# PWR_M_V1.net
KiCad netlist of a schematic drawn in Altium Designer
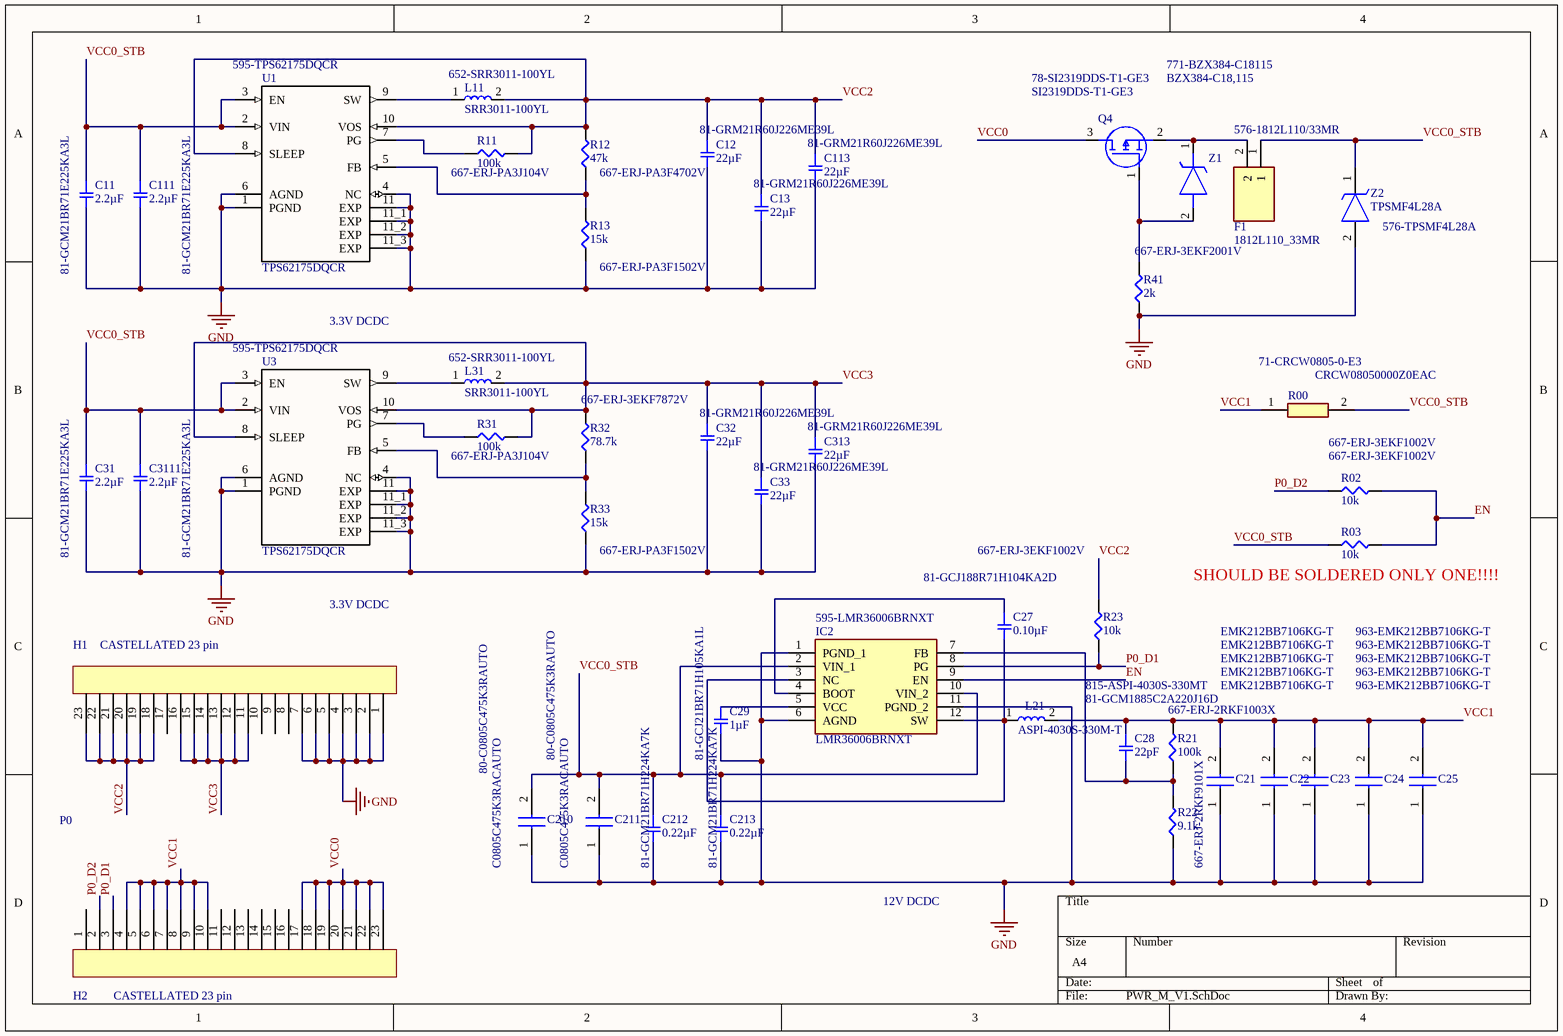
[diagram p0: PWR_M_V1.SchDoc]

(export (version "E")
  (design (tool "Eeschema 10.0.6"))
  (components
    (comp (ref "C11")
      (value "2.2µF")
      (footprint "SMD-0805C")
      (description "CAP CER 2.2UF 25V X7R 0805")
      (fields
        (field (name "DIGI-KEY PART NUMBER") "490-4787-1-ND")
        (field (name "PART NUMBER") "GCM21BR71E225KA73L")
        (field (name "SUPPLIER PART NUMBER 1") "81-GCM21BR71E225KA3L")
      )
      (libsource (lib "capacitor_murata_0805") (part "GCM21BR71E225KA73L"))
    )
    (comp (ref "C12")
      (value "22µF")
      (footprint "SMD-0805C")
      (description "CAP CER 22UF 6.3V X5R 0805")
      (fields
        (field (name "PART NUMBER") "GRM21BR60J226ME39L")
        (field (name "DIGI-KEY PART NUMBER") "490-1719-1-ND")
        (field (name "SUPPLIER PART NUMBER 1") "81-GRM21R60J226ME39L")
      )
      (libsource (lib "cap_murata") (part "CAPACITOR"))
    )
    (comp (ref "C13")
      (value "22µF")
      (footprint "SMD-0805C")
      (description "CAP CER 22UF 6.3V X5R 0805")
      (fields
        (field (name "PART NUMBER") "GRM21BR60J226ME39L")
        (field (name "DIGI-KEY PART NUMBER") "490-1719-1-ND")
        (field (name "SUPPLIER PART NUMBER 1") "81-GRM21R60J226ME39L")
      )
      (libsource (lib "cap_murata") (part "CAPACITOR"))
    )
    (comp (ref "C21")
      (value "EMK212BB7106KG-T")
      (footprint "SamacSys:CAPC2012X135N")
      (description "Capacitor")
      (fields (field (name "SUPPLIER PART NUMBER 1") "963-EMK212BB7106KG-T"))
      (libsource (lib "*") (part "EMK212BB7106KG-T"))
    )
    (comp (ref "C22")
      (value "EMK212BB7106KG-T")
      (footprint "SamacSys:CAPC2012X135N")
      (description "Capacitor")
      (fields (field (name "SUPPLIER PART NUMBER 1") "963-EMK212BB7106KG-T"))
      (libsource (lib "*") (part "EMK212BB7106KG-T"))
    )
    (comp (ref "C23")
      (value "EMK212BB7106KG-T")
      (footprint "SamacSys:CAPC2012X135N")
      (description "Capacitor")
      (fields (field (name "SUPPLIER PART NUMBER 1") "963-EMK212BB7106KG-T"))
      (libsource (lib "*") (part "EMK212BB7106KG-T"))
    )
    (comp (ref "C24")
      (value "EMK212BB7106KG-T")
      (footprint "SamacSys:CAPC2012X135N")
      (description "Capacitor")
      (fields (field (name "SUPPLIER PART NUMBER 1") "963-EMK212BB7106KG-T"))
      (libsource (lib "*") (part "EMK212BB7106KG-T"))
    )
    (comp (ref "C25")
      (value "EMK212BB7106KG-T")
      (footprint "SamacSys:CAPC2012X135N")
      (description "Capacitor")
      (fields (field (name "SUPPLIER PART NUMBER 1") "963-EMK212BB7106KG-T"))
      (libsource (lib "*") (part "EMK212BB7106KG-T"))
    )
    (comp (ref "C27")
      (value "0.10µF")
      (footprint "SMD-0603C")
      (description "CAP CER 0.1UF 50V X7R 0603")
      (fields
        (field (name "DIGI-KEY PART NUMBER") "490-5798-1-ND")
        (field (name "PART NUMBER") "GCJ188R71H104KA12D")
        (field (name "SUPPLIER PART NUMBER 1") "81-GCJ188R71H104KA2D")
      )
      (libsource (lib "capacitor_murata_0603") (part "GCJ188R71H104KA12D"))
    )
    (comp (ref "C28")
      (value "22pF")
      (footprint "SMD-0603C")
      (description "CAP CER 22PF 100V NP0 0603")
      (fields
        (field (name "DIGI-KEY PART NUMBER") "490-4942-1-ND")
        (field (name "PART NUMBER") "GCM1885C2A220JA16D")
        (field (name "SUPPLIER PART NUMBER 1") "81-GCM1885C2A220J16D")
      )
      (libsource (lib "capacitor_murata_0603") (part "GCM1885C2A220JA16D"))
    )
    (comp (ref "C29")
      (value "1µF")
      (footprint "SMD-0805C")
      (description "CAP CER 1UF 50V X7R 0805")
      (fields
        (field (name "DIGI-KEY PART NUMBER") "490-10667-1-ND")
        (field (name "PART NUMBER") "GCJ21BR71H105KA01L")
        (field (name "SUPPLIER PART NUMBER 1") "81-GCJ21BR71H105KA1L")
      )
      (libsource (lib "capacitor_murata_0805") (part "GCJ21BR71H105KA01L"))
    )
    (comp (ref "C31")
      (value "2.2µF")
      (footprint "SMD-0805C")
      (description "CAP CER 2.2UF 25V X7R 0805")
      (fields
        (field (name "DIGI-KEY PART NUMBER") "490-4787-1-ND")
        (field (name "PART NUMBER") "GCM21BR71E225KA73L")
        (field (name "SUPPLIER PART NUMBER 1") "81-GCM21BR71E225KA3L")
      )
      (libsource (lib "capacitor_murata_0805") (part "GCM21BR71E225KA73L"))
    )
    (comp (ref "C32")
      (value "22µF")
      (footprint "SMD-0805C")
      (description "CAP CER 22UF 6.3V X5R 0805")
      (fields
        (field (name "PART NUMBER") "GRM21BR60J226ME39L")
        (field (name "DIGI-KEY PART NUMBER") "490-1719-1-ND")
        (field (name "SUPPLIER PART NUMBER 1") "81-GRM21R60J226ME39L")
      )
      (libsource (lib "cap_murata") (part "CAPACITOR"))
    )
    (comp (ref "C33")
      (value "22µF")
      (footprint "SMD-0805C")
      (description "CAP CER 22UF 6.3V X5R 0805")
      (fields
        (field (name "PART NUMBER") "GRM21BR60J226ME39L")
        (field (name "DIGI-KEY PART NUMBER") "490-1719-1-ND")
        (field (name "SUPPLIER PART NUMBER 1") "81-GRM21R60J226ME39L")
      )
      (libsource (lib "cap_murata") (part "CAPACITOR"))
    )
    (comp (ref "C111")
      (value "2.2µF")
      (footprint "SMD-0805C")
      (description "CAP CER 2.2UF 25V X7R 0805")
      (fields
        (field (name "DIGI-KEY PART NUMBER") "490-4787-1-ND")
        (field (name "PART NUMBER") "GCM21BR71E225KA73L")
        (field (name "SUPPLIER PART NUMBER 1") "81-GCM21BR71E225KA3L")
      )
      (libsource (lib "capacitor_murata_0805") (part "GCM21BR71E225KA73L"))
    )
    (comp (ref "C113")
      (value "22µF")
      (footprint "SMD-0805C")
      (description "CAP CER 22UF 6.3V X5R 0805")
      (fields
        (field (name "PART NUMBER") "GRM21BR60J226ME39L")
        (field (name "DIGI-KEY PART NUMBER") "490-1719-1-ND")
        (field (name "SUPPLIER PART NUMBER 1") "81-GRM21R60J226ME39L")
      )
      (libsource (lib "cap_murata") (part "CAPACITOR"))
    )
    (comp (ref "C210")
      (value "C0805C475K3RACAUTO")
      (footprint "SamacSys:CAPC2012X125N")
      (description "Capacitor")
      (fields
        (field (name "MOUSER2 PART NUMBER") "80-C0805C475K3RAUTO")
        (field (name "SUPPLIER PART NUMBER 1") "80-C0805C475K3RAUTO")
      )
      (libsource (lib "*") (part "C0805C475K3RACAUTO"))
    )
    (comp (ref "C211")
      (value "C0805C475K3RACAUTO")
      (footprint "SamacSys:CAPC2012X125N")
      (description "Capacitor")
      (fields
        (field (name "MOUSER2 PART NUMBER") "80-C0805C475K3RAUTO")
        (field (name "SUPPLIER PART NUMBER 1") "80-C0805C475K3RAUTO")
      )
      (libsource (lib "*") (part "C0805C475K3RACAUTO"))
    )
    (comp (ref "C212")
      (value "0.22µF")
      (footprint "SMD-0805C")
      (description "CAP CER 0.22UF 50V X7R 0805")
      (fields
        (field (name "DIGI-KEY PART NUMBER") "490-13311-1-ND")
        (field (name "PART NUMBER") "GCM21BR71H224KA37K")
        (field (name "SUPPLIER PART NUMBER 1") "81-GCM21BR71H224KA7K")
      )
      (libsource (lib "capacitor_murata_0805") (part "GCM21BR71H224KA37K"))
    )
    (comp (ref "C213")
      (value "0.22µF")
      (footprint "SMD-0805C")
      (description "CAP CER 0.22UF 50V X7R 0805")
      (fields
        (field (name "DIGI-KEY PART NUMBER") "490-13311-1-ND")
        (field (name "PART NUMBER") "GCM21BR71H224KA37K")
        (field (name "SUPPLIER PART NUMBER 1") "81-GCM21BR71H224KA7K")
      )
      (libsource (lib "capacitor_murata_0805") (part "GCM21BR71H224KA37K"))
    )
    (comp (ref "C313")
      (value "22µF")
      (footprint "SMD-0805C")
      (description "CAP CER 22UF 6.3V X5R 0805")
      (fields
        (field (name "PART NUMBER") "GRM21BR60J226ME39L")
        (field (name "DIGI-KEY PART NUMBER") "490-1719-1-ND")
        (field (name "SUPPLIER PART NUMBER 1") "81-GRM21R60J226ME39L")
      )
      (libsource (lib "cap_murata") (part "CAPACITOR"))
    )
    (comp (ref "C3111")
      (value "2.2µF")
      (footprint "SMD-0805C")
      (description "CAP CER 2.2UF 25V X7R 0805")
      (fields
        (field (name "DIGI-KEY PART NUMBER") "490-4787-1-ND")
        (field (name "PART NUMBER") "GCM21BR71E225KA73L")
        (field (name "SUPPLIER PART NUMBER 1") "81-GCM21BR71E225KA3L")
      )
      (libsource (lib "capacitor_murata_0805") (part "GCM21BR71E225KA73L"))
    )
    (comp (ref "F1")
      (value "1812L110_33MR")
      (footprint "SamacSys:FUSC4632X200N")
      (description "Fuse")
      (fields
        (field (name "MOUSER2 PART NUMBER") "576-1812L110/33MR")
        (field (name "MANUFACTURER_PART_NUMBER") "1812L110/33MR")
        (field (name "SUPPLIER PART NUMBER 1") "576-1812L110/33MR")
      )
      (libsource (lib "*") (part "1812L110_33MR"))
    )
    (comp (ref "H1")
      (value "CASTELLATED 23 pin")
      (footprint "CASTELLATED 23 pin")
      (libsource (lib "") (part "CASTELLATED 23 pin_1"))
    )
    (comp (ref "H2")
      (value "CASTELLATED 23 pin")
      (footprint "CASTELLATED 23 pin")
      (libsource (lib "USIB") (part "CASTELLATED 23 pin"))
    )
    (comp (ref "IC2")
      (value "LMR36006BRNXT")
      (footprint "SamacSys:LMR36015FSCQRNXTQ1")
      (description "Integrated Circuit")
      (fields
        (field (name "MOUSER2 PART NUMBER") "595-LMR36006BRNXT")
        (field (name "SUPPLIER PART NUMBER 1") "595-LMR36006BRNXT")
      )
      (libsource (lib "*") (part "LMR36006BRNXT"))
    )
    (comp (ref "L11")
      (value "SRR3011-100YL")
      (footprint "SRR3011-100YL")
      (fields (field (name "SUPPLIER PART NUMBER 1") "652-SRR3011-100YL"))
      (libsource (lib "SRR3011-100YL") (part "SRR3011-100YL"))
    )
    (comp (ref "L21")
      (value "ASPI-4030S-330M-T")
      (footprint "INDPM4040X300N")
      (fields (field (name "SUPPLIER PART NUMBER 1") "815-ASPI-4030S-330MT"))
      (libsource (lib "SamacSys") (part "ASPI-4030S-330M-T"))
    )
    (comp (ref "L31")
      (value "SRR3011-100YL")
      (footprint "SRR3011-100YL")
      (fields (field (name "SUPPLIER PART NUMBER 1") "652-SRR3011-100YL"))
      (libsource (lib "SRR3011-100YL") (part "SRR3011-100YL"))
    )
    (comp (ref "Q4")
      (value "SI2319DDS-T1-GE3")
      (footprint "SamacSys:SOT96P240X120-3N")
      (description "MOSFET (P-Channel)")
      (fields (field (name "SUPPLIER PART NUMBER 1") "78-SI2319DDS-T1-GE3"))
      (libsource (lib "*") (part "SI2319DDS-T1-GE3"))
    )
    (comp (ref "R00")
      (value "CRCW08050000Z0EAC")
      (footprint "SamacSys:RESC2012X60N")
      (description "Resistor")
      (fields
        (field (name "MOUSER2 PART NUMBER") "71-CRCW08050000Z0EAC")
        (field (name "SUPPLIER PART NUMBER 1") "71-CRCW0805-0-E3")
      )
      (libsource (lib "*") (part "CRCW08050000Z0EAC"))
    )
    (comp (ref "R02")
      (value "10k")
      (footprint "SMD-0603-RES")
      (description "RES SMD 10K OHM 1% 1/10W 0603")
      (fields
        (field (name "PART NUMBER") "ERJ-3EKF1002V")
        (field (name "DIGI-KEY PART NUMBER") "P10.0KHCT-ND")
        (field (name "SUPPLIER PART NUMBER 1") "667-ERJ-3EKF1002V")
      )
      (libsource (lib "Panasonic_ERJ_0603") (part "ERJ-3EKF1002V"))
    )
    (comp (ref "R03")
      (value "10k")
      (footprint "SMD-0603-RES")
      (description "RES SMD 10K OHM 1% 1/10W 0603")
      (fields
        (field (name "PART NUMBER") "ERJ-3EKF1002V")
        (field (name "DIGI-KEY PART NUMBER") "P10.0KHCT-ND")
        (field (name "SUPPLIER PART NUMBER 1") "667-ERJ-3EKF1002V")
      )
      (libsource (lib "Panasonic_ERJ_0603") (part "ERJ-3EKF1002V"))
    )
    (comp (ref "R11")
      (value "100k")
      (footprint "SMD-0603-RES")
      (description "RES SMD 100K OHM 5% 1/4W 0603")
      (fields
        (field (name "PART NUMBER") "ERJ-PA3J104V")
        (field (name "DIGI-KEY PART NUMBER") "P100KBZCT-ND")
        (field (name "SUPPLIER PART NUMBER 1") "667-ERJ-PA3J104V")
      )
      (libsource (lib "Panasonic_ERJ_0603") (part "ERJ-PA3J104V"))
    )
    (comp (ref "R12")
      (value "47k")
      (footprint "SMD-0603-RES")
      (description "RES SMD 47K OHM 1% 1/4W 0603")
      (fields
        (field (name "PART NUMBER") "ERJ-PA3F4702V")
        (field (name "DIGI-KEY PART NUMBER") "P47KBYCT-ND")
        (field (name "SUPPLIER PART NUMBER 1") "667-ERJ-PA3F4702V")
      )
      (libsource (lib "Panasonic_ERJ_0603") (part "ERJ-PA3F4702V"))
    )
    (comp (ref "R13")
      (value "15k")
      (footprint "SMD-0603-RES")
      (description "RES SMD 15K OHM 1% 1/4W 0603")
      (fields
        (field (name "PART NUMBER") "ERJ-PA3F1502V")
        (field (name "DIGI-KEY PART NUMBER") "P15KBYCT-ND")
        (field (name "SUPPLIER PART NUMBER 1") "667-ERJ-PA3F1502V")
      )
      (libsource (lib "Panasonic_ERJ_0603") (part "ERJ-PA3F1502V"))
    )
    (comp (ref "R21")
      (value "100k")
      (footprint "SMD-0402-RES")
      (description "RES SMD 100K OHM 1% 1/10W 0402")
      (fields
        (field (name "PART NUMBER") "ERJ-2RKF1003X")
        (field (name "DIGI-KEY PART NUMBER") "P100KLCT-ND")
        (field (name "SUPPLIER PART NUMBER 1") "667-ERJ-2RKF1003X")
      )
      (libsource (lib "Panasonic_ERJ_0402") (part "ERJ-2RKF1003X"))
    )
    (comp (ref "R22")
      (value "9.1k")
      (footprint "SMD-0402-RES")
      (description "RES SMD 9.1K OHM 1% 1/10W 0402")
      (fields
        (field (name "PART NUMBER") "ERJ-2RKF9101X")
        (field (name "DIGI-KEY PART NUMBER") "P9.10KLCT-ND")
        (field (name "SUPPLIER PART NUMBER 1") "667-ERJ-2RKF9101X")
      )
      (libsource (lib "Panasonic_ERJ_0402") (part "ERJ-2RKF9101X"))
    )
    (comp (ref "R23")
      (value "10k")
      (footprint "SMD-0603-RES")
      (description "RES SMD 10K OHM 1% 1/10W 0603")
      (fields
        (field (name "PART NUMBER") "ERJ-3EKF1002V")
        (field (name "DIGI-KEY PART NUMBER") "P10.0KHCT-ND")
        (field (name "SUPPLIER PART NUMBER 1") "667-ERJ-3EKF1002V")
      )
      (libsource (lib "Panasonic_ERJ_0603") (part "ERJ-3EKF1002V"))
    )
    (comp (ref "R31")
      (value "100k")
      (footprint "SMD-0603-RES")
      (description "RES SMD 100K OHM 5% 1/4W 0603")
      (fields
        (field (name "PART NUMBER") "ERJ-PA3J104V")
        (field (name "DIGI-KEY PART NUMBER") "P100KBZCT-ND")
        (field (name "SUPPLIER PART NUMBER 1") "667-ERJ-PA3J104V")
      )
      (libsource (lib "Panasonic_ERJ_0603") (part "ERJ-PA3J104V"))
    )
    (comp (ref "R32")
      (value "78.7k")
      (footprint "SMD-0603-RES")
      (description "RES SMD 78.7K OHM 1% 1/10W 0603")
      (fields
        (field (name "PART NUMBER") "ERJ-3EKF7872V")
        (field (name "DIGI-KEY PART NUMBER") "P78.7KHCT-ND")
        (field (name "SUPPLIER PART NUMBER 1") "667-ERJ-3EKF7872V")
      )
      (libsource (lib "Panasonic_ERJ_0603") (part "ERJ-3EKF7872V"))
    )
    (comp (ref "R33")
      (value "15k")
      (footprint "SMD-0603-RES")
      (description "RES SMD 15K OHM 1% 1/4W 0603")
      (fields
        (field (name "PART NUMBER") "ERJ-PA3F1502V")
        (field (name "DIGI-KEY PART NUMBER") "P15KBYCT-ND")
        (field (name "SUPPLIER PART NUMBER 1") "667-ERJ-PA3F1502V")
      )
      (libsource (lib "Panasonic_ERJ_0603") (part "ERJ-PA3F1502V"))
    )
    (comp (ref "R41")
      (value "2k")
      (footprint "SMD-0603-RES")
      (description "RES SMD 2K OHM 1% 1/10W 0603")
      (fields
        (field (name "PART NUMBER") "ERJ-3EKF2001V")
        (field (name "DIGI-KEY PART NUMBER") "P2.00KHCT-ND")
        (field (name "SUPPLIER PART NUMBER 1") "667-ERJ-3EKF2001V")
      )
      (libsource (lib "Panasonic_ERJ_0603") (part "ERJ-3EKF2001V"))
    )
    (comp (ref "U1")
      (value "TPS62175DQCR")
      (footprint "*SON50P300X200X80-11N240X84_TPS62175DQCR(Primary)")
      (description "28V, 0.5A Step-Down Converter with SNOOZE Mode 10-WSON -40 to 85")
      (fields
        (field (name "MF") "Texas Instruments")
        (field (name "SUPPLIER PART NUMBER 1") "595-TPS62175DQCR")
      )
      (libsource (lib "TPS62175DQCR") (part "TPS62175DQCR"))
    )
    (comp (ref "U3")
      (value "TPS62175DQCR")
      (footprint "*SON50P300X200X80-11N240X84_TPS62175DQCR(Primary)")
      (description "28V, 0.5A Step-Down Converter with SNOOZE Mode 10-WSON -40 to 85")
      (fields
        (field (name "MF") "Texas Instruments")
        (field (name "SUPPLIER PART NUMBER 1") "595-TPS62175DQCR")
      )
      (libsource (lib "TPS62175DQCR") (part "TPS62175DQCR"))
    )
    (comp (ref "Z1")
      (value "BZX384-C18,115")
      (footprint "SamacSys:SOD2512X110N")
      (description "Zener Diode")
      (fields
        (field (name "MOUSER2 PART NUMBER") "771-BZX384-C18115")
        (field (name "SUPPLIER PART NUMBER 1") "771-BZX384-C18115")
      )
      (libsource (lib "*") (part "BZX384-C18,115"))
    )
    (comp (ref "Z2")
      (value "TPSMF4L28A")
      (footprint "SamacSys:SODFL3718X108N")
      (description "TVS Diode (Uni-directional)")
      (fields (field (name "SUPPLIER PART NUMBER 1") "576-TPSMF4L28A"))
      (libsource (lib "*") (part "TPSMF4L28A"))
    )
  )
  (nets
    (net (code "1") (name "/EN") (class "Default")
      (node (ref "IC2") (pin "9") (pinfunction "EN_9") (pintype "passive"))
      (node (ref "R02") (pin "2") (pinfunction "2_2") (pintype "passive"))
      (node (ref "R03") (pin "2") (pinfunction "2_2") (pintype "passive"))
    )
    (net (code "2") (name "/P0_D1") (class "Default")
      (node (ref "H2") (pin "3") (pintype "passive"))
      (node (ref "IC2") (pin "8") (pinfunction "PG_8") (pintype "passive"))
      (node (ref "R23") (pin "1") (pinfunction "1_1") (pintype "passive"))
    )
    (net (code "3") (name "/P0_D2") (class "Default")
      (node (ref "H2") (pin "2") (pintype "passive"))
      (node (ref "R02") (pin "1") (pinfunction "1_1") (pintype "passive"))
    )
    (net (code "4") (name "/VCC0") (class "Default")
      (node (ref "H2") (pin "17") (pintype "passive"))
      (node (ref "H2") (pin "18") (pintype "passive"))
      (node (ref "H2") (pin "19") (pintype "passive"))
      (node (ref "H2") (pin "20") (pintype "passive"))
      (node (ref "H2") (pin "21") (pintype "passive"))
      (node (ref "H2") (pin "22") (pintype "passive"))
      (node (ref "H2") (pin "23") (pintype "passive"))
      (node (ref "Q4") (pin "3") (pinfunction "D_3") (pintype "passive"))
    )
    (net (code "5") (name "/VCC0_STB") (class "Default")
      (node (ref "C11") (pin "1") (pinfunction "1_1") (pintype "passive"))
      (node (ref "C111") (pin "1") (pinfunction "1_1") (pintype "passive"))
      (node (ref "C210") (pin "2") (pinfunction "2_2") (pintype "passive"))
      (node (ref "C211") (pin "2") (pinfunction "2_2") (pintype "passive"))
      (node (ref "C212") (pin "1") (pinfunction "1_1") (pintype "passive"))
      (node (ref "C213") (pin "1") (pinfunction "1_1") (pintype "passive"))
      (node (ref "C31") (pin "1") (pinfunction "1_1") (pintype "passive"))
      (node (ref "C3111") (pin "1") (pinfunction "1_1") (pintype "passive"))
      (node (ref "F1") (pin "1") (pinfunction "1_1") (pintype "passive"))
      (node (ref "IC2") (pin "10") (pinfunction "VIN_2_10") (pintype "passive"))
      (node (ref "IC2") (pin "2") (pinfunction "VIN_1_2") (pintype "passive"))
      (node (ref "R00") (pin "2") (pinfunction "2_2") (pintype "passive"))
      (node (ref "R03") (pin "1") (pinfunction "1_1") (pintype "passive"))
      (node (ref "U1") (pin "2") (pinfunction "VIN_2") (pintype "input"))
      (node (ref "U1") (pin "3") (pinfunction "EN_3") (pintype "input"))
      (node (ref "U3") (pin "2") (pinfunction "VIN_2") (pintype "input"))
      (node (ref "U3") (pin "3") (pinfunction "EN_3") (pintype "input"))
      (node (ref "Z2") (pin "1") (pinfunction "K_1") (pintype "passive"))
    )
    (net (code "6") (name "/VCC1") (class "Default")
      (node (ref "C21") (pin "2") (pinfunction "2_2") (pintype "passive"))
      (node (ref "C22") (pin "2") (pinfunction "2_2") (pintype "passive"))
      (node (ref "C23") (pin "2") (pinfunction "2_2") (pintype "passive"))
      (node (ref "C24") (pin "2") (pinfunction "2_2") (pintype "passive"))
      (node (ref "C25") (pin "2") (pinfunction "2_2") (pintype "passive"))
      (node (ref "C28") (pin "1") (pinfunction "1_1") (pintype "passive"))
      (node (ref "H2") (pin "10") (pintype "passive"))
      (node (ref "H2") (pin "4") (pintype "passive"))
      (node (ref "H2") (pin "5") (pintype "passive"))
      (node (ref "H2") (pin "6") (pintype "passive"))
      (node (ref "H2") (pin "7") (pintype "passive"))
      (node (ref "H2") (pin "8") (pintype "passive"))
      (node (ref "H2") (pin "9") (pintype "passive"))
      (node (ref "L21") (pin "2") (pinfunction "2_2") (pintype "passive"))
      (node (ref "R00") (pin "1") (pinfunction "1_1") (pintype "passive"))
      (node (ref "R21") (pin "2") (pinfunction "2_2") (pintype "passive"))
    )
    (net (code "7") (name "/VCC2") (class "Default")
      (node (ref "C113") (pin "1") (pinfunction "1_1") (pintype "passive"))
      (node (ref "C12") (pin "1") (pinfunction "1_1") (pintype "passive"))
      (node (ref "C13") (pin "1") (pinfunction "1_1") (pintype "passive"))
      (node (ref "H1") (pin "18") (pintype "passive"))
      (node (ref "H1") (pin "19") (pintype "passive"))
      (node (ref "H1") (pin "20") (pintype "passive"))
      (node (ref "H1") (pin "21") (pintype "passive"))
      (node (ref "H1") (pin "22") (pintype "passive"))
      (node (ref "H1") (pin "23") (pintype "passive"))
      (node (ref "L11") (pin "2") (pinfunction "2_2") (pintype "passive"))
      (node (ref "R11") (pin "2") (pinfunction "2_2") (pintype "passive"))
      (node (ref "R12") (pin "2") (pinfunction "2_2") (pintype "passive"))
      (node (ref "R23") (pin "2") (pinfunction "2_2") (pintype "passive"))
      (node (ref "U1") (pin "10") (pinfunction "VOS_10") (pintype "input"))
      (node (ref "U1") (pin "8") (pinfunction "SLEEP_8") (pintype "input"))
    )
    (net (code "8") (name "/VCC3") (class "Default")
      (node (ref "C313") (pin "1") (pinfunction "1_1") (pintype "passive"))
      (node (ref "C32") (pin "1") (pinfunction "1_1") (pintype "passive"))
      (node (ref "C33") (pin "1") (pinfunction "1_1") (pintype "passive"))
      (node (ref "H1") (pin "11") (pintype "passive"))
      (node (ref "H1") (pin "12") (pintype "passive"))
      (node (ref "H1") (pin "13") (pintype "passive"))
      (node (ref "H1") (pin "14") (pintype "passive"))
      (node (ref "H1") (pin "15") (pintype "passive"))
      (node (ref "H1") (pin "16") (pintype "passive"))
      (node (ref "L31") (pin "2") (pinfunction "2_2") (pintype "passive"))
      (node (ref "R31") (pin "2") (pinfunction "2_2") (pintype "passive"))
      (node (ref "R32") (pin "2") (pinfunction "2_2") (pintype "passive"))
      (node (ref "U3") (pin "10") (pinfunction "VOS_10") (pintype "input"))
      (node (ref "U3") (pin "8") (pinfunction "SLEEP_8") (pintype "input"))
    )
    (net (code "9") (name "GND") (class "Default")
      (node (ref "C11") (pin "2") (pinfunction "2_2") (pintype "passive"))
      (node (ref "C111") (pin "2") (pinfunction "2_2") (pintype "passive"))
      (node (ref "C113") (pin "2") (pinfunction "2_2") (pintype "passive"))
      (node (ref "C12") (pin "2") (pinfunction "2_2") (pintype "passive"))
      (node (ref "C13") (pin "2") (pinfunction "2_2") (pintype "passive"))
      (node (ref "C21") (pin "1") (pinfunction "1_1") (pintype "passive"))
      (node (ref "C210") (pin "1") (pinfunction "1_1") (pintype "passive"))
      (node (ref "C211") (pin "1") (pinfunction "1_1") (pintype "passive"))
      (node (ref "C212") (pin "2") (pinfunction "2_2") (pintype "passive"))
      (node (ref "C213") (pin "2") (pinfunction "2_2") (pintype "passive"))
      (node (ref "C22") (pin "1") (pinfunction "1_1") (pintype "passive"))
      (node (ref "C23") (pin "1") (pinfunction "1_1") (pintype "passive"))
      (node (ref "C24") (pin "1") (pinfunction "1_1") (pintype "passive"))
      (node (ref "C25") (pin "1") (pinfunction "1_1") (pintype "passive"))
      (node (ref "C29") (pin "2") (pinfunction "2_2") (pintype "passive"))
      (node (ref "C31") (pin "2") (pinfunction "2_2") (pintype "passive"))
      (node (ref "C3111") (pin "2") (pinfunction "2_2") (pintype "passive"))
      (node (ref "C313") (pin "2") (pinfunction "2_2") (pintype "passive"))
      (node (ref "C32") (pin "2") (pinfunction "2_2") (pintype "passive"))
      (node (ref "C33") (pin "2") (pinfunction "2_2") (pintype "passive"))
      (node (ref "H1") (pin "1") (pintype "passive"))
      (node (ref "H1") (pin "2") (pintype "passive"))
      (node (ref "H1") (pin "3") (pintype "passive"))
      (node (ref "H1") (pin "4") (pintype "passive"))
      (node (ref "H1") (pin "5") (pintype "passive"))
      (node (ref "H1") (pin "6") (pintype "passive"))
      (node (ref "H1") (pin "7") (pintype "passive"))
      (node (ref "IC2") (pin "1") (pinfunction "PGND_1_1") (pintype "passive"))
      (node (ref "IC2") (pin "11") (pinfunction "PGND_2_11") (pintype "passive"))
      (node (ref "IC2") (pin "6") (pinfunction "AGND_6") (pintype "passive"))
      (node (ref "R13") (pin "1") (pinfunction "1_1") (pintype "passive"))
      (node (ref "R22") (pin "1") (pinfunction "1_1") (pintype "passive"))
      (node (ref "R33") (pin "1") (pinfunction "1_1") (pintype "passive"))
      (node (ref "R41") (pin "1") (pinfunction "1_1") (pintype "passive"))
      (node (ref "U1") (pin "1") (pinfunction "PGND_1") (pintype "power_in"))
      (node (ref "U1") (pin "11") (pinfunction "EXP_11") (pintype "power_in"))
      (node (ref "U1") (pin "11_1") (pinfunction "EXP_11_1") (pintype "power_in"))
      (node (ref "U1") (pin "11_2") (pinfunction "EXP_11_2") (pintype "power_in"))
      (node (ref "U1") (pin "11_3") (pinfunction "EXP_11_3") (pintype "power_in"))
      (node (ref "U1") (pin "4") (pinfunction "NC_4") (pintype "bidirectional"))
      (node (ref "U1") (pin "6") (pinfunction "AGND_6") (pintype "power_in"))
      (node (ref "U3") (pin "1") (pinfunction "PGND_1") (pintype "power_in"))
      (node (ref "U3") (pin "11") (pinfunction "EXP_11") (pintype "power_in"))
      (node (ref "U3") (pin "11_1") (pinfunction "EXP_11_1") (pintype "power_in"))
      (node (ref "U3") (pin "11_2") (pinfunction "EXP_11_2") (pintype "power_in"))
      (node (ref "U3") (pin "11_3") (pinfunction "EXP_11_3") (pintype "power_in"))
      (node (ref "U3") (pin "4") (pinfunction "NC_4") (pintype "bidirectional"))
      (node (ref "U3") (pin "6") (pinfunction "AGND_6") (pintype "power_in"))
      (node (ref "Z2") (pin "2") (pinfunction "A_2") (pintype "passive"))
    )
    (net (code "10") (name "Net-(IC2-BOOT)") (class "Default")
      (node (ref "C27") (pin "1") (pinfunction "1_1") (pintype "passive"))
      (node (ref "IC2") (pin "4") (pinfunction "BOOT_4") (pintype "passive"))
    )
    (net (code "11") (name "Net-(IC2-FB)") (class "Default")
      (node (ref "C28") (pin "2") (pinfunction "2_2") (pintype "passive"))
      (node (ref "IC2") (pin "7") (pinfunction "FB_7") (pintype "passive"))
      (node (ref "R21") (pin "1") (pinfunction "1_1") (pintype "passive"))
      (node (ref "R22") (pin "2") (pinfunction "2_2") (pintype "passive"))
    )
    (net (code "12") (name "Net-(IC2-NC)") (class "Default")
      (node (ref "C27") (pin "2") (pinfunction "2_2") (pintype "passive"))
      (node (ref "IC2") (pin "12") (pinfunction "SW_12") (pintype "passive"))
      (node (ref "IC2") (pin "3") (pinfunction "NC_3") (pintype "passive"))
      (node (ref "L21") (pin "1") (pinfunction "1_1") (pintype "passive"))
    )
    (net (code "13") (name "Net-(IC2-VCC)") (class "Default")
      (node (ref "C29") (pin "1") (pinfunction "1_1") (pintype "passive"))
      (node (ref "IC2") (pin "5") (pinfunction "VCC_5") (pintype "passive"))
    )
    (net (code "14") (name "Net-(Q4-G)") (class "Default")
      (node (ref "Q4") (pin "1") (pinfunction "G_1") (pintype "passive"))
      (node (ref "R41") (pin "2") (pinfunction "2_2") (pintype "passive"))
      (node (ref "Z1") (pin "2") (pinfunction "A_2") (pintype "passive"))
    )
    (net (code "15") (name "Net-(Q4-S)") (class "Default")
      (node (ref "F1") (pin "2") (pinfunction "2_2") (pintype "passive"))
      (node (ref "Q4") (pin "2") (pinfunction "S_2") (pintype "passive"))
      (node (ref "Z1") (pin "1") (pinfunction "K_1") (pintype "passive"))
    )
    (net (code "16") (name "Net-(U1-FB)") (class "Default")
      (node (ref "R12") (pin "1") (pinfunction "1_1") (pintype "passive"))
      (node (ref "R13") (pin "2") (pinfunction "2_2") (pintype "passive"))
      (node (ref "U1") (pin "5") (pinfunction "FB_5") (pintype "input"))
    )
    (net (code "17") (name "Net-(U1-PG)") (class "Default")
      (node (ref "R11") (pin "1") (pinfunction "1_1") (pintype "passive"))
      (node (ref "U1") (pin "7") (pinfunction "PG_7") (pintype "output"))
    )
    (net (code "18") (name "Net-(U1-SW)") (class "Default")
      (node (ref "L11") (pin "1") (pinfunction "1_1") (pintype "passive"))
      (node (ref "U1") (pin "9") (pinfunction "SW_9") (pintype "output"))
    )
    (net (code "19") (name "Net-(U3-FB)") (class "Default")
      (node (ref "R32") (pin "1") (pinfunction "1_1") (pintype "passive"))
      (node (ref "R33") (pin "2") (pinfunction "2_2") (pintype "passive"))
      (node (ref "U3") (pin "5") (pinfunction "FB_5") (pintype "input"))
    )
    (net (code "20") (name "Net-(U3-PG)") (class "Default")
      (node (ref "R31") (pin "1") (pinfunction "1_1") (pintype "passive"))
      (node (ref "U3") (pin "7") (pinfunction "PG_7") (pintype "output"))
    )
    (net (code "21") (name "Net-(U3-SW)") (class "Default")
      (node (ref "L31") (pin "1") (pinfunction "1_1") (pintype "passive"))
      (node (ref "U3") (pin "9") (pinfunction "SW_9") (pintype "output"))
    )
    (net (code "22") (name "unconnected-(H1-Pad8)") (class "Default")
      (node (ref "H1") (pin "8") (pintype "passive"))
    )
    (net (code "23") (name "unconnected-(H1-Pad9)") (class "Default")
      (node (ref "H1") (pin "9") (pintype "passive"))
    )
    (net (code "24") (name "unconnected-(H1-Pad10)") (class "Default")
      (node (ref "H1") (pin "10") (pintype "passive"))
    )
    (net (code "25") (name "unconnected-(H1-Pad17)") (class "Default")
      (node (ref "H1") (pin "17") (pintype "passive"))
    )
    (net (code "26") (name "unconnected-(H2-Pad1)") (class "Default")
      (node (ref "H2") (pin "1") (pintype "passive"))
    )
    (net (code "27") (name "unconnected-(H2-Pad11)") (class "Default")
      (node (ref "H2") (pin "11") (pintype "passive"))
    )
    (net (code "28") (name "unconnected-(H2-Pad12)") (class "Default")
      (node (ref "H2") (pin "12") (pintype "passive"))
    )
    (net (code "29") (name "unconnected-(H2-Pad13)") (class "Default")
      (node (ref "H2") (pin "13") (pintype "passive"))
    )
    (net (code "30") (name "unconnected-(H2-Pad14)") (class "Default")
      (node (ref "H2") (pin "14") (pintype "passive"))
    )
    (net (code "31") (name "unconnected-(H2-Pad15)") (class "Default")
      (node (ref "H2") (pin "15") (pintype "passive"))
    )
    (net (code "32") (name "unconnected-(H2-Pad16)") (class "Default")
      (node (ref "H2") (pin "16") (pintype "passive"))
    )
  )
)
